# hv_io_DCDC.net
KiCad netlist of a schematic drawn in Altium Designer
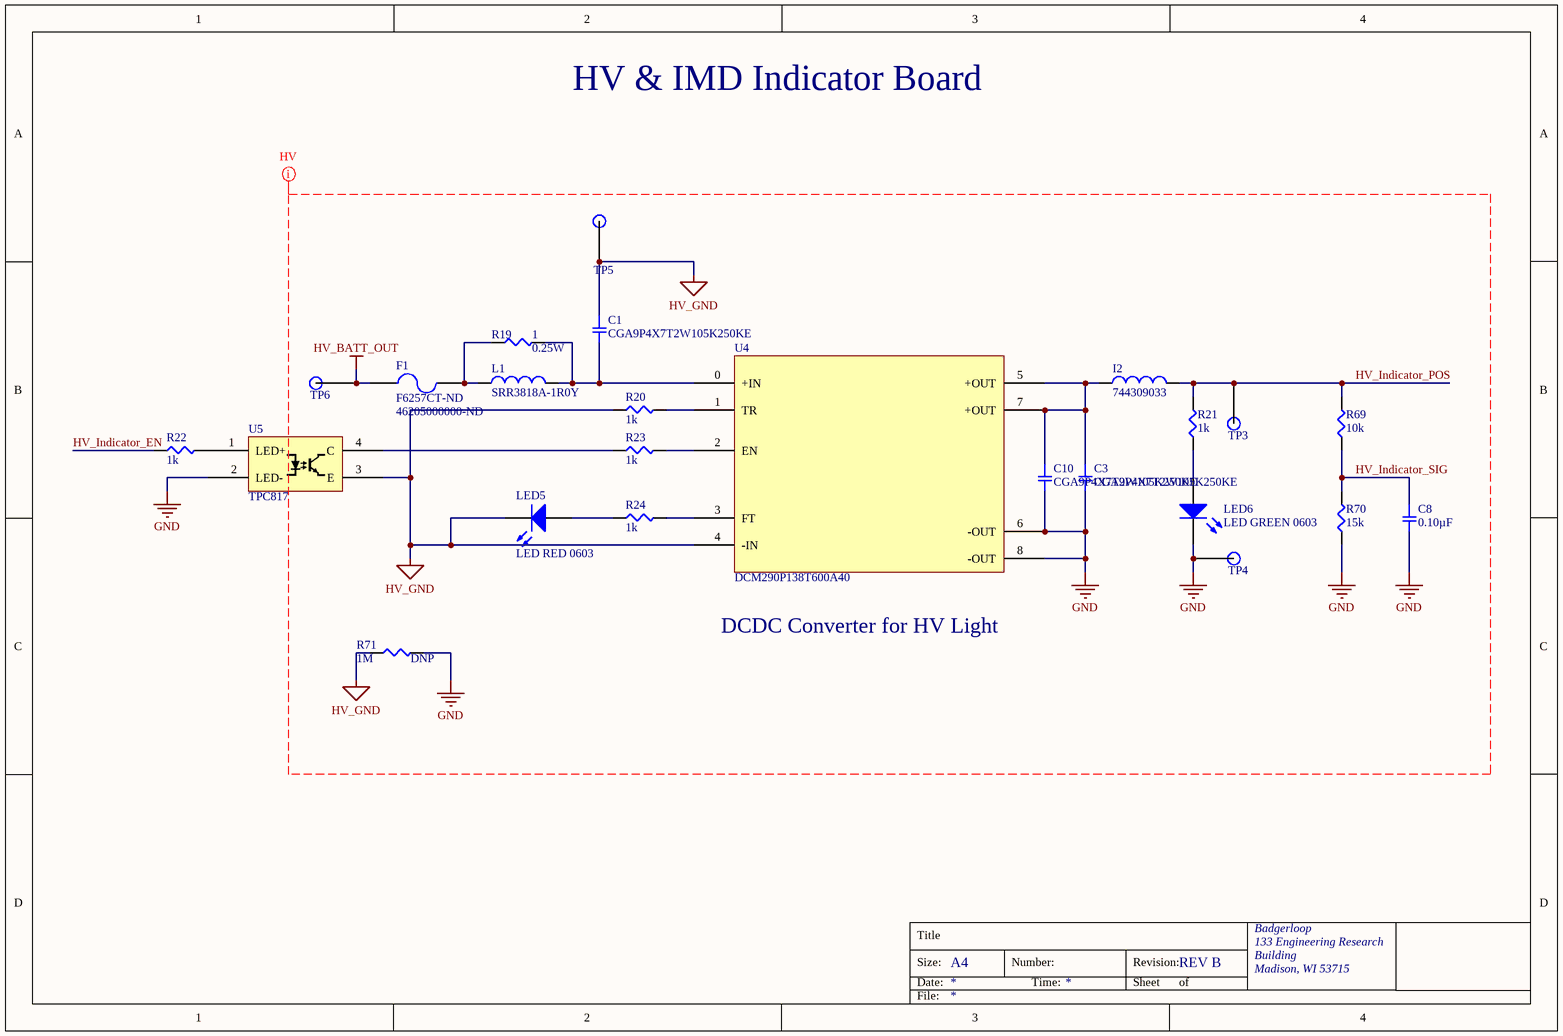
[diagram p0: hv_io_DCDC.SchDoc]

(export (version "E")
  (design (tool "Eeschema 10.0.6"))
  (components
    (comp (ref "C1")
      (value "CGA9P4X7T2W105K250KE")
      (footprint "CAPC8350X15N")
      (description "CAP CER 1UF 450V X7T 2220")
      (fields (field (name "MANUFACTURER") "TDK"))
      (libsource (lib "temp") (part "CGA9P4X7T2W105K250KE"))
    )
    (comp (ref "C3")
      (value "CGA9P4X7T2W105K250KE")
      (footprint "CAPC8350X15N")
      (description "CAP CER 1UF 450V X7T 2220")
      (fields (field (name "MANUFACTURER") "TDK"))
      (libsource (lib "temp") (part "CGA9P4X7T2W105K250KE"))
    )
    (comp (ref "C8")
      (value "0.10µF")
      (footprint "SMD-0805C")
      (description "CAP CER 0.1UF 50V X7R 0805")
      (fields
        (field (name "PART NUMBER") "GCD21BR71H104KA01L")
        (field (name "MANUFACTURER") "Murata Electronics North America")
      )
      (libsource (lib "altium-import") (part "root_0_GCD21BR71H104KA01L_"))
    )
    (comp (ref "C10")
      (value "CGA9P4X7T2W105K250KE")
      (footprint "CAPC8350X15N")
      (description "CAP CER 1UF 450V X7T 2220")
      (fields (field (name "MANUFACTURER") "TDK"))
      (libsource (lib "temp") (part "CGA9P4X7T2W105K250KE"))
    )
    (comp (ref "F1")
      (value "F6257CT-ND")
      (footprint "F6257CT-ND")
      (description "FUSE BOARD MNT 500MA 350VAC/VDC")
      (fields
        (field (name "MANUFACTURER") "Littelfuse")
        (field (name "MANUFACTURER PART NUMBER") "46205000000")
        (field (name "SUPPLIER PART NUMBER 1") "46205000000-ND")
      )
      (libsource (lib "misc") (part "F6257CT-ND"))
    )
    (comp (ref "I2")
      (value "744309033")
      (footprint "INDM140130X90N")
      (description "FIXED IND 330NH 47.5A 0.165 MOHM")
      (fields (field (name "MANUFACTURER") "Wurth"))
      (libsource (lib "temp") (part "744309033"))
    )
    (comp (ref "L1")
      (value "SRR3818A-1R0Y")
      (footprint "INDM3838X18N")
      (description "FIXED IND 1UH 3.6A 37 MOHM SMD")
      (fields (field (name "MANUFACTURER") "Bourns Inc."))
      (libsource (lib "temp") (part "SRR3818A-1R0Y"))
    )
    (comp (ref "LED5")
      (value "LED RED 0603")
      (footprint "LED 0603 RED")
      (description "Red 631nm LED Indication - Discrete 2V 0603 (1608 Metric)")
      (fields (field (name "MANUFACTURER") "Lite-On Inc."))
      (libsource (lib "misc") (part "LED RED 0603"))
    )
    (comp (ref "LED6")
      (value "LED GREEN 0603")
      (footprint "LED 0603 GREEN")
      (fields (field (name "MANUFACTURER") "Lite-On Inc."))
      (libsource (lib "misc") (part "LED GREEN 0603"))
    )
    (comp (ref "R19")
      (value "1")
      (footprint "SMD-1206-RES")
      (description "RES SMD 1 OHM 1% 1/4W 1206")
      (fields
        (field (name "PART NUMBER") "ERJ-8RQF1R0V")
        (field (name "DIGI-KEY PART NUMBER") "P1.0RCT-ND")
        (field (name "POWER (WATTS)") "0.25W")
      )
      (libsource (lib "resistor") (part "ERJ-8RQF1R0V"))
    )
    (comp (ref "R20")
      (value "1k")
      (footprint "SMD-0805-RES")
      (description "RES SMD 1K OHM 1% 1/8W 0805")
      (fields
        (field (name "PART NUMBER") "ERJ-6ENF1001V")
        (field (name "DIGI-KEY PART NUMBER") "P1.00KCCT-ND")
      )
      (libsource (lib "resistor") (part "ERJ-6ENF1001V"))
    )
    (comp (ref "R21")
      (value "1k")
      (footprint "SMD-0805-RES")
      (description "RES SMD 1K OHM 1% 1/8W 0805")
      (fields
        (field (name "PART NUMBER") "ERJ-6ENF1001V")
        (field (name "DIGI-KEY PART NUMBER") "P1.00KCCT-ND")
      )
      (libsource (lib "resistor") (part "ERJ-6ENF1001V"))
    )
    (comp (ref "R22")
      (value "1k")
      (footprint "SMD-0805-RES")
      (description "RES SMD 1K OHM 1% 1/8W 0805")
      (fields
        (field (name "PART NUMBER") "ERJ-6ENF1001V")
        (field (name "DIGI-KEY PART NUMBER") "P1.00KCCT-ND")
      )
      (libsource (lib "resistor") (part "ERJ-6ENF1001V"))
    )
    (comp (ref "R23")
      (value "1k")
      (footprint "SMD-0805-RES")
      (description "RES SMD 1K OHM 1% 1/8W 0805")
      (fields
        (field (name "PART NUMBER") "ERJ-6ENF1001V")
        (field (name "DIGI-KEY PART NUMBER") "P1.00KCCT-ND")
      )
      (libsource (lib "resistor") (part "ERJ-6ENF1001V"))
    )
    (comp (ref "R24")
      (value "1k")
      (footprint "SMD-0805-RES")
      (description "RES SMD 1K OHM 1% 1/8W 0805")
      (fields
        (field (name "PART NUMBER") "ERJ-6ENF1001V")
        (field (name "DIGI-KEY PART NUMBER") "P1.00KCCT-ND")
      )
      (libsource (lib "resistor") (part "ERJ-6ENF1001V"))
    )
    (comp (ref "R69")
      (value "10k")
      (footprint "SMD-0805-RES")
      (description "RES SMD 10K OHM 5% 1/2W 0805")
      (fields (field (name "PART NUMBER") "ERJ-P06J103V") (field (name "DIGI-KEY PART NUMBER") "P10KADCT-ND"))
      (libsource (lib "altium-import") (part "root_1_ERJ-P06J103V_"))
    )
    (comp (ref "R70")
      (value "15k")
      (footprint "SMD-0805-RES")
      (description "RES SMD 15K OHM 5% 1/2W 0805")
      (fields (field (name "PART NUMBER") "ERJ-P06J153V") (field (name "DIGI-KEY PART NUMBER") "P15KADCT-ND"))
      (libsource (lib "altium-import") (part "root_1_ERJ-P06J153V_"))
    )
    (comp (ref "R71")
      (value "1M")
      (footprint "SMD-1206-RES")
      (description "RES SMD 1M OHM 5% 2/3W 1206")
      (fields
        (field (name "PART NUMBER") "ERJ-P08J105V")
        (field (name "DIGI-KEY PART NUMBER") "P1.0MALCT-ND")
        (field (name "DNP") "DNP")
      )
      (libsource (lib "resistor") (part "ERJ-P08J105V"))
    )
    (comp (ref "TP3") (value "TP") (footprint "Test Point") (libsource (lib "misc") (part "TP")))
    (comp (ref "TP4") (value "TP") (footprint "Test Point") (libsource (lib "misc") (part "TP")))
    (comp (ref "TP5") (value "TP") (footprint "Test Point") (libsource (lib "misc") (part "TP")))
    (comp (ref "TP6") (value "TP") (footprint "Test Point") (libsource (lib "misc") (part "TP")))
    (comp (ref "U4")
      (value "DCM290P138T600A40")
      (footprint "DCM290y138x600A40")
      (description "DC DC CONVERTER 13.8V 600W")
      (fields (field (name "MANUFACTURER") "Vicor"))
      (libsource (lib "ic") (part "DCM290P138T600A40"))
    )
    (comp (ref "U5")
      (value "TPC817")
      (footprint "SOT200P1005X328-5N")
      (description "OPTOISO 5KV TRANS 4SOP")
      (fields (field (name "MANUFACTURER") "Taiwan Semi"))
      (libsource (lib "ic") (part "TPC817"))
    )
  )
  (nets
    (net (code "2") (name "/HV_Indicator_EN") (class "Default")
      (node (ref "R22") (pin "1") (pinfunction "1_1") (pintype "passive"))
    )
    (net (code "3") (name "/HV_Indicator_POS") (class "Default")
      (node (ref "I2") (pin "2") (pinfunction "2_2") (pintype "passive"))
      (node (ref "R21") (pin "2") (pinfunction "2_2") (pintype "passive"))
      (node (ref "R69") (pin "2") (pinfunction "2_2") (pintype "passive"))
      (node (ref "TP3") (pin "1") (pinfunction "1_1") (pintype "passive"))
    )
    (net (code "4") (name "/HV_Indicator_SIG") (class "Default")
      (node (ref "C8") (pin "1") (pinfunction "1_1") (pintype "passive"))
      (node (ref "R69") (pin "1") (pinfunction "1_1") (pintype "passive"))
      (node (ref "R70") (pin "2") (pinfunction "2_2") (pintype "passive"))
    )
    (net (code "5") (name "GND") (class "Default")
      (node (ref "C10") (pin "2") (pinfunction "2_2") (pintype "passive"))
      (node (ref "C3") (pin "2") (pinfunction "2_2") (pintype "passive"))
      (node (ref "C8") (pin "2") (pinfunction "2_2") (pintype "passive"))
      (node (ref "LED6") (pin "2") (pinfunction "K_2") (pintype "passive"))
      (node (ref "R70") (pin "1") (pinfunction "1_1") (pintype "passive"))
      (node (ref "R71") (pin "2") (pinfunction "2_2") (pintype "passive"))
      (node (ref "TP4") (pin "1") (pinfunction "1_1") (pintype "passive"))
      (node (ref "U4") (pin "6") (pinfunction "-OUT_6") (pintype "passive"))
      (node (ref "U4") (pin "8") (pinfunction "-OUT_8") (pintype "passive"))
      (node (ref "U5") (pin "2") (pinfunction "LED-_2") (pintype "passive"))
    )
    (net (code "6") (name "HV_BATT_OUT") (class "Default")
      (node (ref "F1") (pin "1") (pinfunction "1_1") (pintype "passive"))
      (node (ref "TP6") (pin "1") (pinfunction "1_1") (pintype "passive"))
    )
    (net (code "7") (name "HV_GND") (class "Default")
      (node (ref "C1") (pin "1") (pinfunction "1_1") (pintype "passive"))
      (node (ref "LED5") (pin "2") (pinfunction "K_2") (pintype "passive"))
      (node (ref "R20") (pin "1") (pinfunction "1_1") (pintype "passive"))
      (node (ref "R71") (pin "1") (pinfunction "1_1") (pintype "passive"))
      (node (ref "TP5") (pin "1") (pinfunction "1_1") (pintype "passive"))
      (node (ref "U4") (pin "4") (pinfunction "-IN_4") (pintype "passive"))
      (node (ref "U5") (pin "3") (pinfunction "E_3") (pintype "passive"))
    )
    (net (code "8") (name "Net-(C10-Pad1)") (class "Default")
      (node (ref "C10") (pin "1") (pinfunction "1_1") (pintype "passive"))
      (node (ref "C3") (pin "1") (pinfunction "1_1") (pintype "passive"))
      (node (ref "I2") (pin "1") (pinfunction "1_1") (pintype "passive"))
      (node (ref "U4") (pin "5") (pinfunction "+OUT_5") (pintype "passive"))
      (node (ref "U4") (pin "7") (pinfunction "+OUT_7") (pintype "passive"))
    )
    (net (code "9") (name "Net-(F1-Pad2)") (class "Default")
      (node (ref "F1") (pin "2") (pinfunction "2_2") (pintype "passive"))
      (node (ref "L1") (pin "1") (pinfunction "1_1") (pintype "passive"))
      (node (ref "R19") (pin "1") (pinfunction "1_1") (pintype "passive"))
    )
    (net (code "10") (name "Net-(LED5-A)") (class "Default")
      (node (ref "LED5") (pin "1") (pinfunction "A_1") (pintype "passive"))
      (node (ref "R24") (pin "1") (pinfunction "1_1") (pintype "passive"))
    )
    (net (code "11") (name "Net-(LED6-A)") (class "Default")
      (node (ref "LED6") (pin "1") (pinfunction "A_1") (pintype "passive"))
      (node (ref "R21") (pin "1") (pinfunction "1_1") (pintype "passive"))
    )
    (net (code "12") (name "Net-(U4-+IN)") (class "Default")
      (node (ref "C1") (pin "2") (pinfunction "2_2") (pintype "passive"))
      (node (ref "L1") (pin "2") (pinfunction "2_2") (pintype "passive"))
      (node (ref "R19") (pin "2") (pinfunction "2_2") (pintype "passive"))
      (node (ref "U4") (pin "0") (pinfunction "+IN_0") (pintype "passive"))
    )
    (net (code "13") (name "Net-(U4-EN)") (class "Default")
      (node (ref "R23") (pin "2") (pinfunction "2_2") (pintype "passive"))
      (node (ref "U4") (pin "2") (pinfunction "EN_2") (pintype "passive"))
    )
    (net (code "14") (name "Net-(U4-FT)") (class "Default")
      (node (ref "R24") (pin "2") (pinfunction "2_2") (pintype "passive"))
      (node (ref "U4") (pin "3") (pinfunction "FT_3") (pintype "passive"))
    )
    (net (code "15") (name "Net-(U4-TR)") (class "Default")
      (node (ref "R20") (pin "2") (pinfunction "2_2") (pintype "passive"))
      (node (ref "U4") (pin "1") (pinfunction "TR_1") (pintype "passive"))
    )
    (net (code "16") (name "Net-(U5-C)") (class "Default")
      (node (ref "R23") (pin "1") (pinfunction "1_1") (pintype "passive"))
      (node (ref "U5") (pin "4") (pinfunction "C_4") (pintype "passive"))
    )
    (net (code "17") (name "Net-(U5-LED+)") (class "Default")
      (node (ref "R22") (pin "2") (pinfunction "2_2") (pintype "passive"))
      (node (ref "U5") (pin "1") (pinfunction "LED+_1") (pintype "passive"))
    )
  )
)
